# ProProject__245__2023-08-28.net
KiCad netlist of a schematic drawn in EasyEDA Pro
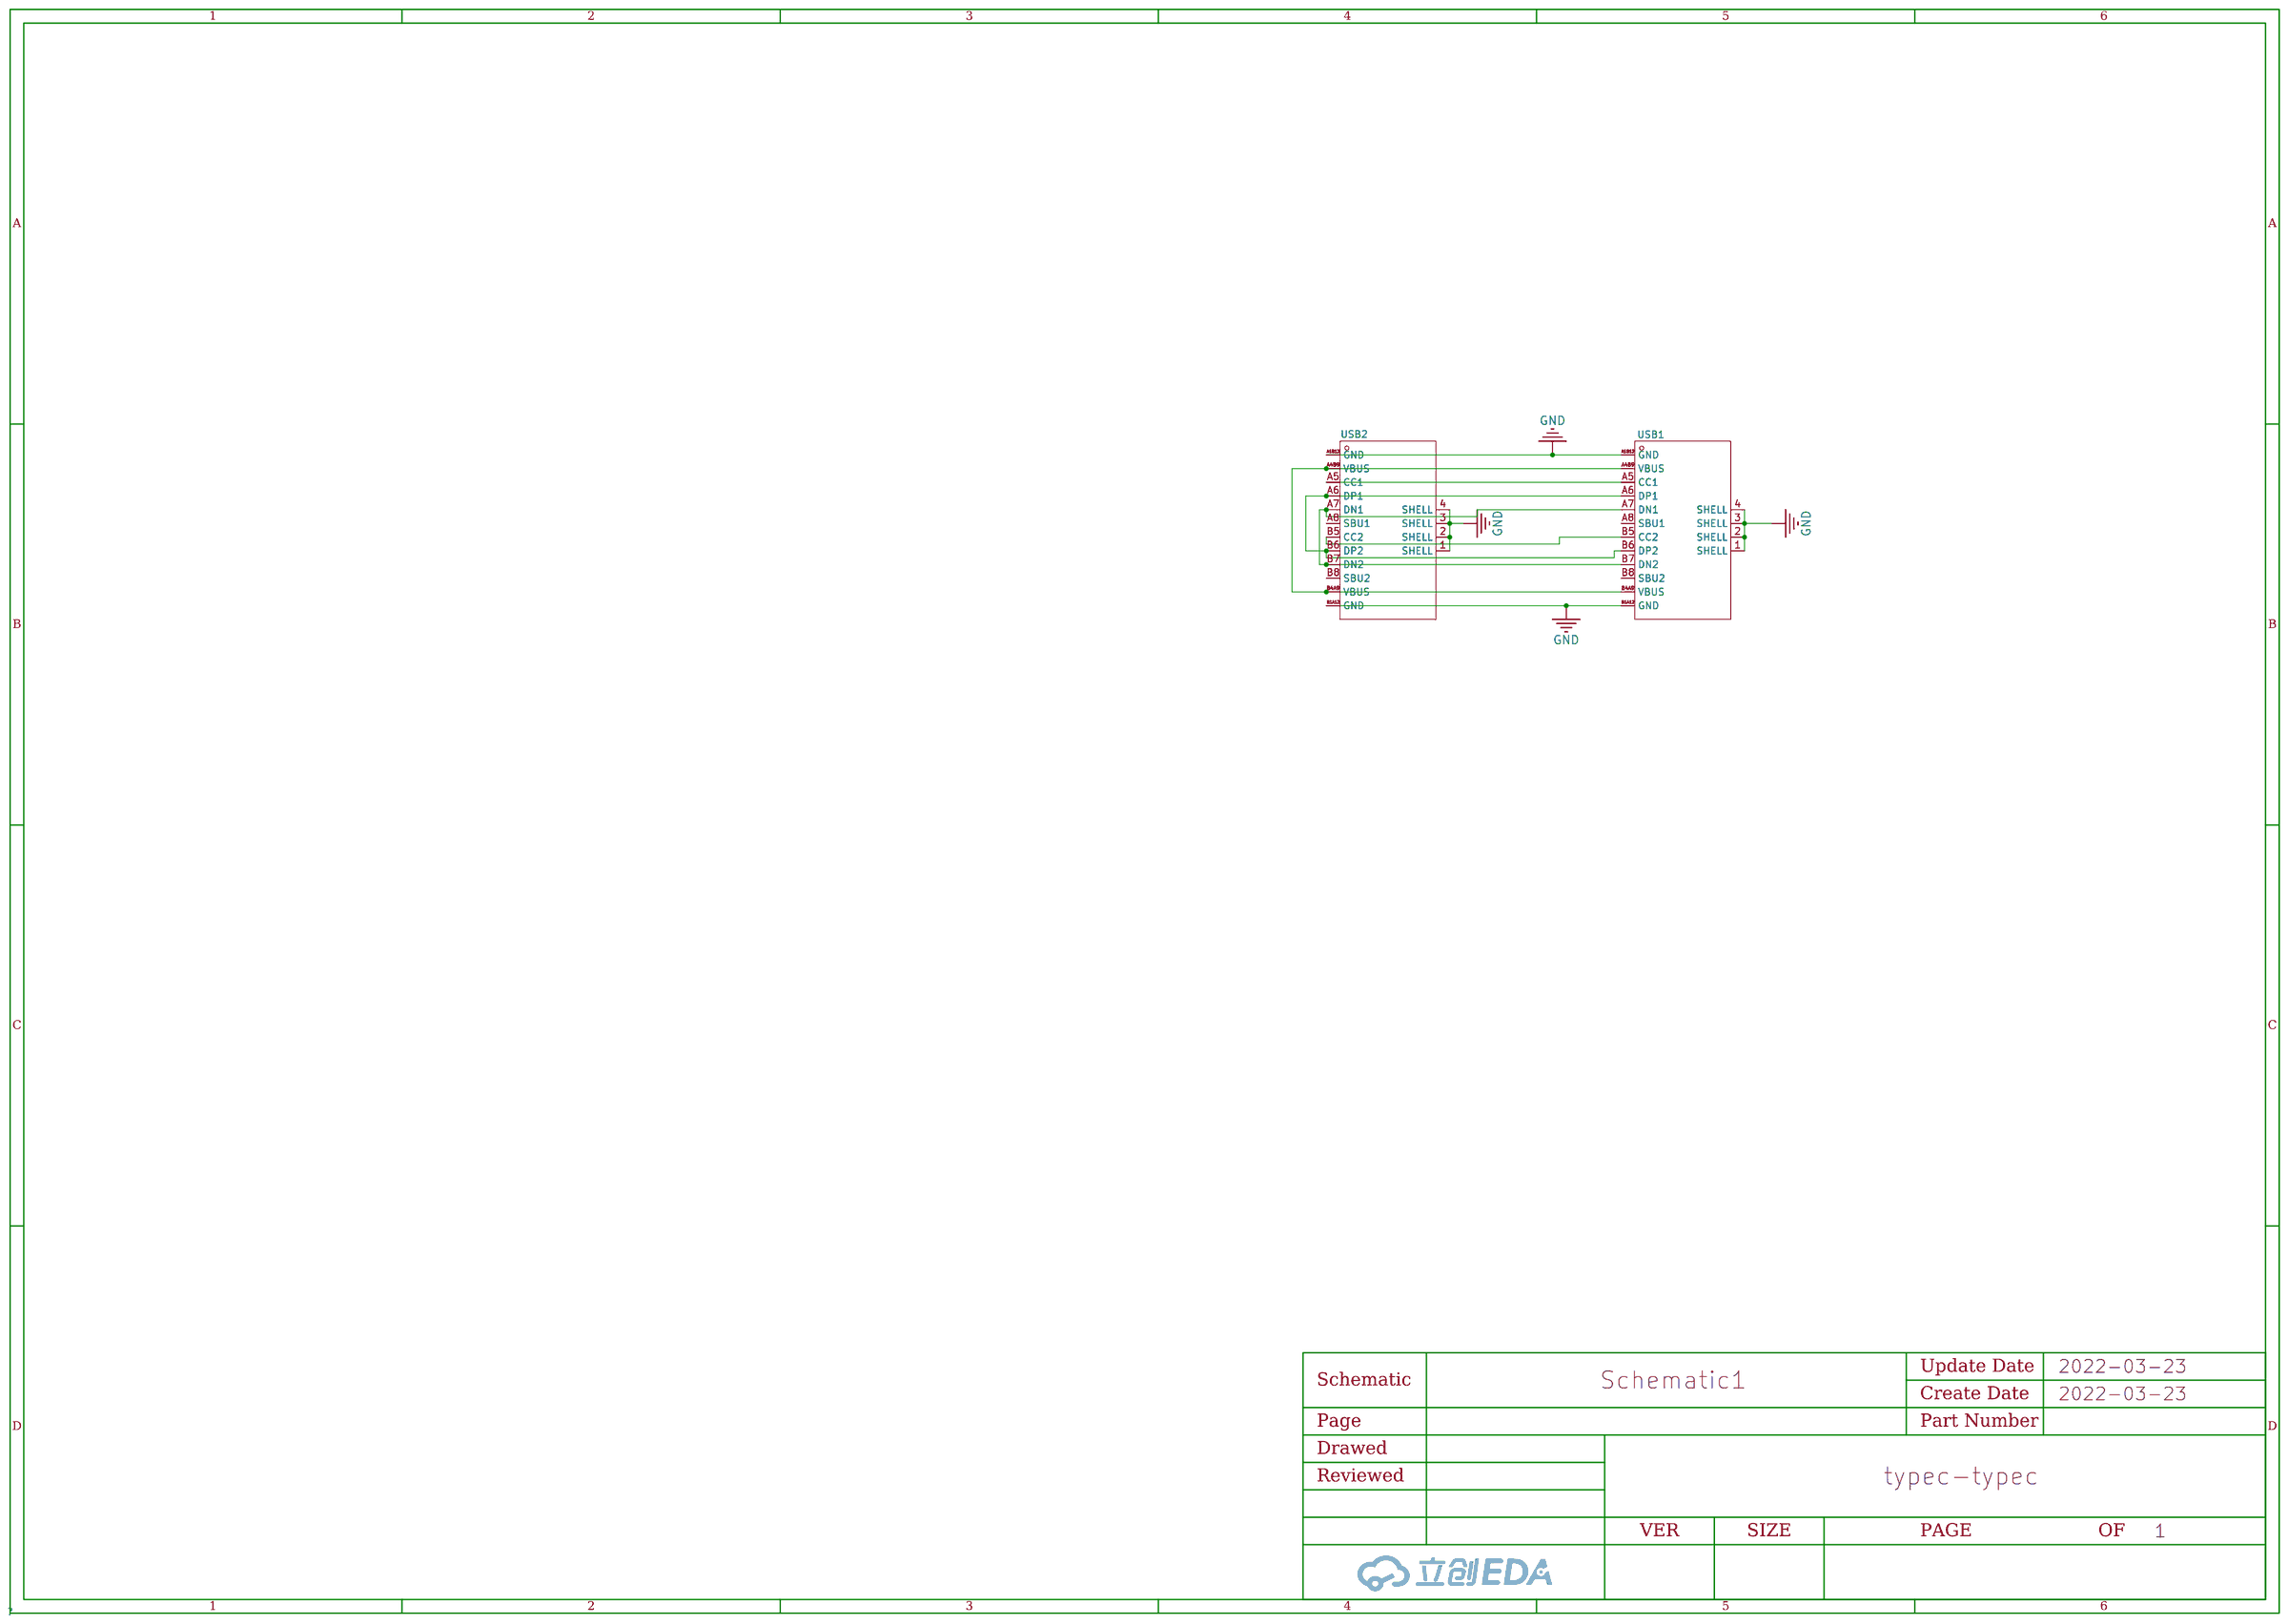
[diagram p0: schematic sheet]

(export (version "E")
  (design (tool "Eeschema 10.0.6"))
  (components
    (comp (ref "USB1")
      (value "~")
      (footprint "easyedapro:USB-C-SMD_TYPE-C16PIN")
      (fields (field (name "Manufacturer Part") "TYPEC12PINCONN"))
      (libsource (lib "easyedapro") (part "TYPEC12PINCONN"))
    )
    (comp (ref "USB2")
      (value "~")
      (footprint "easyedapro:USB-C-SMD_TYPE-C16PIN")
      (fields (field (name "Manufacturer Part") "TYPEC12PINCONN"))
      (libsource (lib "easyedapro") (part "TYPEC12PINCONN"))
    )
  )
  (nets
    (net (code "1") (name "GND") (class "Default")
      (node (ref "USB1") (pin "1") (pinfunction "SHELL_1") (pintype "input"))
      (node (ref "USB1") (pin "2") (pinfunction "SHELL_2") (pintype "input"))
      (node (ref "USB1") (pin "3") (pinfunction "SHELL_3") (pintype "input"))
      (node (ref "USB1") (pin "4") (pinfunction "SHELL_4") (pintype "input"))
      (node (ref "USB1") (pin "A1B12") (pinfunction "GND_A1B12") (pintype "input"))
      (node (ref "USB1") (pin "B1A12") (pinfunction "GND_B1A12") (pintype "input"))
      (node (ref "USB2") (pin "1") (pinfunction "SHELL_1") (pintype "input"))
      (node (ref "USB2") (pin "2") (pinfunction "SHELL_2") (pintype "input"))
      (node (ref "USB2") (pin "3") (pinfunction "SHELL_3") (pintype "input"))
      (node (ref "USB2") (pin "4") (pinfunction "SHELL_4") (pintype "input"))
      (node (ref "USB2") (pin "A1B12") (pinfunction "GND_A1B12") (pintype "input"))
      (node (ref "USB2") (pin "B1A12") (pinfunction "GND_B1A12") (pintype "input"))
    )
    (net (code "2") (name "Net-(USB1-CC1)") (class "Default")
      (node (ref "USB1") (pin "A5") (pinfunction "CC1_A5") (pintype "input"))
      (node (ref "USB2") (pin "A5") (pinfunction "CC1_A5") (pintype "input"))
    )
    (net (code "3") (name "Net-(USB1-CC2)") (class "Default")
      (node (ref "USB1") (pin "B5") (pinfunction "CC2_B5") (pintype "input"))
      (node (ref "USB2") (pin "B5") (pinfunction "CC2_B5") (pintype "input"))
    )
    (net (code "4") (name "Net-(USB1-DN1)") (class "Default")
      (node (ref "USB1") (pin "A7") (pinfunction "DN1_A7") (pintype "input"))
      (node (ref "USB1") (pin "B7") (pinfunction "DN2_B7") (pintype "input"))
      (node (ref "USB2") (pin "A7") (pinfunction "DN1_A7") (pintype "input"))
      (node (ref "USB2") (pin "B7") (pinfunction "DN2_B7") (pintype "input"))
    )
    (net (code "5") (name "Net-(USB1-DP1)") (class "Default")
      (node (ref "USB1") (pin "A6") (pinfunction "DP1_A6") (pintype "input"))
      (node (ref "USB1") (pin "B6") (pinfunction "DP2_B6") (pintype "input"))
      (node (ref "USB2") (pin "A6") (pinfunction "DP1_A6") (pintype "input"))
      (node (ref "USB2") (pin "B6") (pinfunction "DP2_B6") (pintype "input"))
    )
    (net (code "6") (name "Net-(USB1-VBUS-PadA4B9)") (class "Default")
      (node (ref "USB1") (pin "A4B9") (pinfunction "VBUS_A4B9") (pintype "input"))
      (node (ref "USB1") (pin "B4A9") (pinfunction "VBUS_B4A9") (pintype "input"))
      (node (ref "USB2") (pin "A4B9") (pinfunction "VBUS_A4B9") (pintype "input"))
      (node (ref "USB2") (pin "B4A9") (pinfunction "VBUS_B4A9") (pintype "input"))
    )
    (net (code "7") (name "unconnected-(USB1-SBU1-PadA8)") (class "Default")
      (node (ref "USB1") (pin "A8") (pinfunction "SBU1_A8") (pintype "input"))
    )
    (net (code "8") (name "unconnected-(USB1-SBU2-PadB8)") (class "Default")
      (node (ref "USB1") (pin "B8") (pinfunction "SBU2_B8") (pintype "input"))
    )
    (net (code "9") (name "unconnected-(USB2-SBU1-PadA8)") (class "Default")
      (node (ref "USB2") (pin "A8") (pinfunction "SBU1_A8") (pintype "input"))
    )
    (net (code "10") (name "unconnected-(USB2-SBU2-PadB8)") (class "Default")
      (node (ref "USB2") (pin "B8") (pinfunction "SBU2_B8") (pintype "input"))
    )
  )
)
